# Schem_fcvv01.net
KiCad netlist of a schematic drawn in Altium Designer
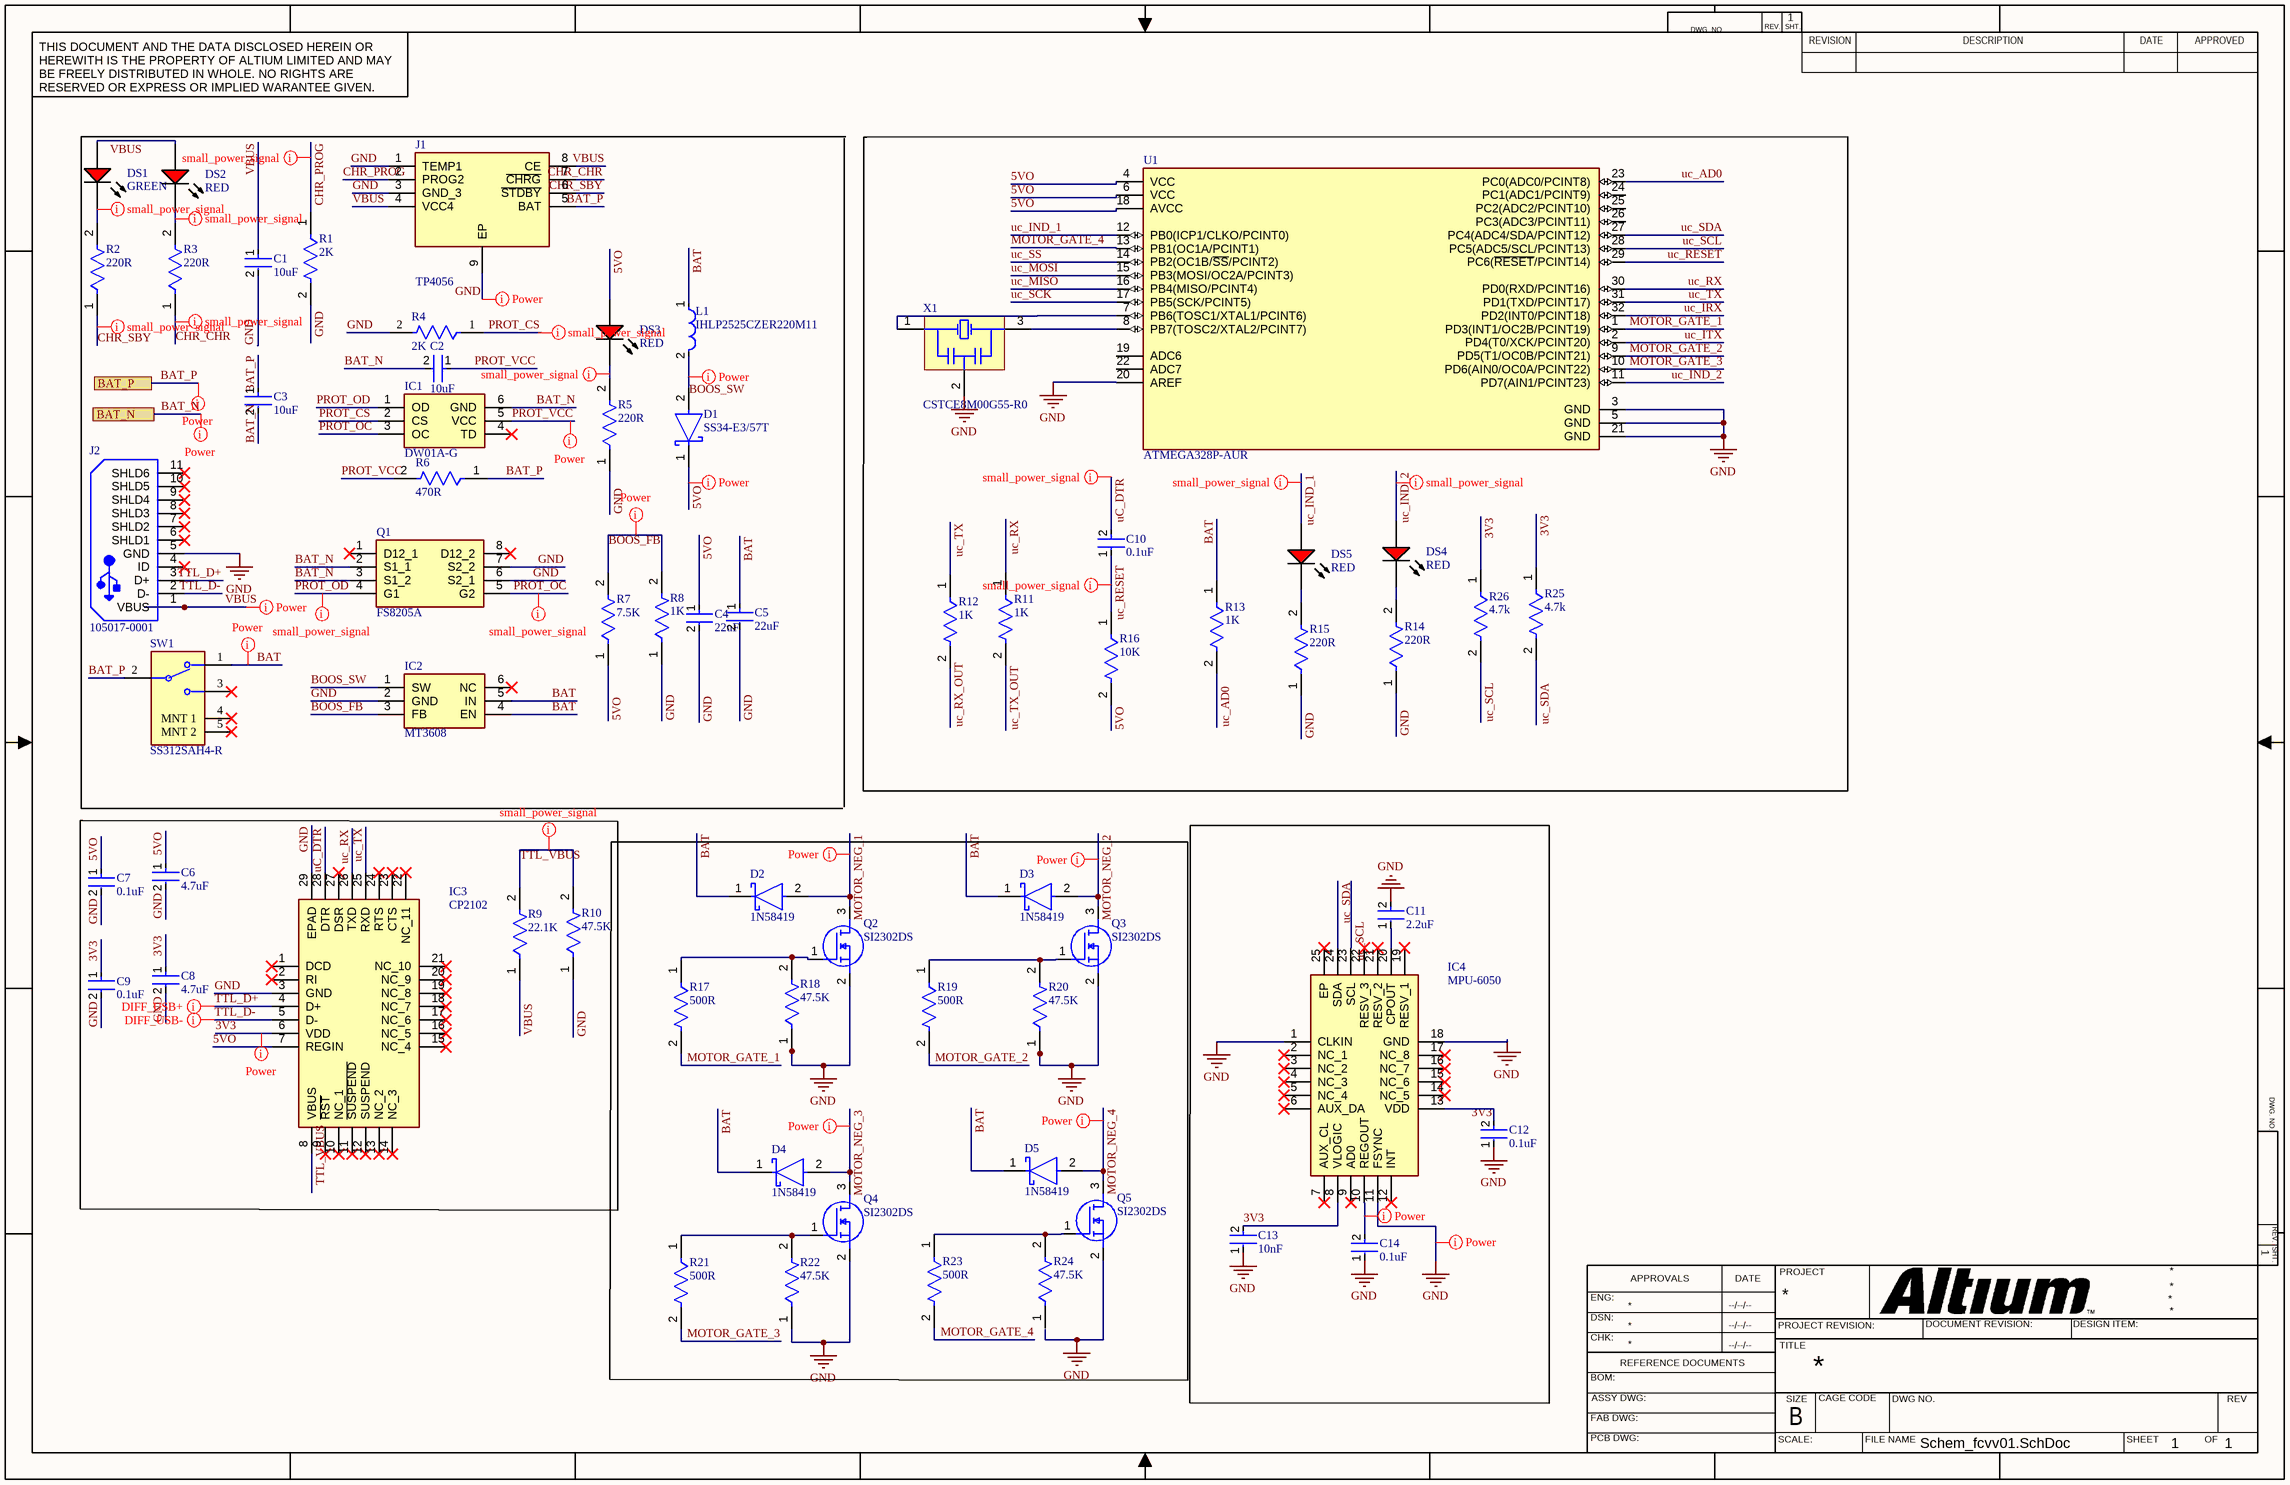
[diagram p0: Schem_fcvv01.SchDoc]

(export (version "E")
  (design (tool "Eeschema 10.0.6"))
  (components
    (comp (ref "C1")
      (value "10uF")
      (footprint "FP-GRM188-0_1-e0_2_0_55-IPC_A")
      (description "10uF 0603")
      (fields (field (name "VOLTAGE") "6.3V") (field (name "TOLERANCE") "20%"))
      (libsource (lib "Altium Content Vault") (part "02cd4be3c70576c341d710602a673aa"))
    )
    (comp (ref "C2")
      (value "10uF")
      (footprint "FP-GRM188-0_1-e0_2_0_55-IPC_A")
      (description "10uF 0603")
      (fields (field (name "VOLTAGE") "6.3V") (field (name "TOLERANCE") "20%"))
      (libsource (lib "Altium Content Vault") (part "02cd4be3c70576c341d710602a673aa"))
    )
    (comp (ref "C3")
      (value "10uF")
      (footprint "FP-GRM188-0_1-e0_2_0_55-IPC_A")
      (description "0603")
      (fields (field (name "VOLTAGE") "6.3V") (field (name "TOLERANCE") "20%"))
      (libsource (lib "Altium Content Vault") (part "02cd4be3c70576c341d710602a673aa"))
    )
    (comp (ref "C4")
      (value "22uF")
      (footprint "FP-GRM188-0_1-e0_2_0_55-IPC_A")
      (description "10uF 0603")
      (fields (field (name "VOLTAGE") "6.3V") (field (name "TOLERANCE") "20%"))
      (libsource (lib "Altium Content Vault") (part "02cd4be3c70576c341d710602a673aa"))
    )
    (comp (ref "C5")
      (value "22uF")
      (footprint "FP-GRM188-0_1-e0_2_0_55-IPC_A")
      (description "10uF 0603")
      (fields (field (name "VOLTAGE") "6.3V") (field (name "TOLERANCE") "20%"))
      (libsource (lib "Altium Content Vault") (part "02cd4be3c70576c341d710602a673aa"))
    )
    (comp (ref "C6")
      (value "4.7uF")
      (footprint "FP-GRM188-0_1-e0_2_0_55-IPC_A")
      (description "0603")
      (fields (field (name "VOLTAGE") "6.3V") (field (name "TOLERANCE") "20%"))
      (libsource (lib "Altium Content Vault") (part "02cd4be3c70576c341d710602a673aa"))
    )
    (comp (ref "C7")
      (value "0.1uF")
      (footprint "FP-GRM188-0_1-e0_2_0_55-IPC_A")
      (description "0603")
      (fields (field (name "VOLTAGE") "6.3V") (field (name "TOLERANCE") "20%"))
      (libsource (lib "Altium Content Vault") (part "02cd4be3c70576c341d710602a673aa"))
    )
    (comp (ref "C8")
      (value "4.7uF")
      (footprint "FP-GRM188-0_1-e0_2_0_55-IPC_A")
      (description "0603")
      (fields (field (name "VOLTAGE") "6.3V") (field (name "TOLERANCE") "20%"))
      (libsource (lib "Altium Content Vault") (part "02cd4be3c70576c341d710602a673aa"))
    )
    (comp (ref "C9")
      (value "0.1uF")
      (footprint "FP-GRM188-0_1-e0_2_0_55-IPC_A")
      (description "0603")
      (fields (field (name "VOLTAGE") "6.3V") (field (name "TOLERANCE") "20%"))
      (libsource (lib "Altium Content Vault") (part "02cd4be3c70576c341d710602a673aa"))
    )
    (comp (ref "C10")
      (value "0.1uF")
      (footprint "FP-GRM15-MFG")
      (description "CAP CER 0.1UF 16V X7R 0402")
      (fields (field (name "MANUFACTURER PART NUMBER") "GRM155R71C104KA88D") (field (name "TOLERANCE") "10%"))
      (libsource (lib "Altium Content Vault") (part "236180d848d6139a670b325ea6854c9"))
    )
    (comp (ref "C11")
      (value "2.2uF")
      (footprint "FP-GRM15-MFG")
      (description "CAP CER 0.1UF 16V X7R 0402")
      (fields (field (name "MANUFACTURER PART NUMBER") "GRM155R71C104KA88D") (field (name "TOLERANCE") "10%"))
      (libsource (lib "Altium Content Vault") (part "236180d848d6139a670b325ea6854c9"))
    )
    (comp (ref "C12")
      (value "0.1uF")
      (footprint "FP-GRM15-MFG")
      (description "CAP CER 0.1UF 16V X7R 0402")
      (fields (field (name "MANUFACTURER PART NUMBER") "GRM155R71C104KA88D") (field (name "TOLERANCE") "10%"))
      (libsource (lib "Altium Content Vault") (part "236180d848d6139a670b325ea6854c9"))
    )
    (comp (ref "C13")
      (value "10nF")
      (footprint "FP-GRM15-MFG")
      (description "CAP CER 0.1UF 16V X7R 0402")
      (fields (field (name "MANUFACTURER PART NUMBER") "GRM155R71C104KA88D") (field (name "TOLERANCE") "10%"))
      (libsource (lib "Altium Content Vault") (part "236180d848d6139a670b325ea6854c9"))
    )
    (comp (ref "C14")
      (value "0.1uF")
      (footprint "FP-GRM15-MFG")
      (description "CAP CER 0.1UF 16V X7R 0402")
      (fields (field (name "MANUFACTURER PART NUMBER") "GRM155R71C104KA88D") (field (name "TOLERANCE") "10%"))
      (libsource (lib "Altium Content Vault") (part "236180d848d6139a670b325ea6854c9"))
    )
    (comp (ref "D1")
      (value "SS34-E3/57T")
      (footprint "FP-95402-MFG")
      (description "DIODE SCHOTTKY 40V 3A DO214AB")
      (fields
        (field (name "MANUFACTURER") "Vishay")
        (field (name "OCTOPART") "https://octopart.com/ss34-e3%2F57t-vishay-39552907")
      )
      (libsource (lib "Altium Content Vault") (part "1d6ec82d83fb6aee721767c19dac4b9"))
    )
    (comp (ref "D2")
      (value "1N58419")
      (footprint "FP-425-04-IPC_C")
      (description "DIODE SCHOTTKY 20V 500MA SOD123")
      (libsource (lib "Altium Content Vault") (part "1d6ec82d83fb6aee721767c19dac4b9"))
    )
    (comp (ref "D3")
      (value "1N58419")
      (footprint "FP-425-04-IPC_C")
      (description "DIODE SCHOTTKY 20V 500MA SOD123")
      (libsource (lib "Altium Content Vault") (part "1d6ec82d83fb6aee721767c19dac4b9"))
    )
    (comp (ref "D4")
      (value "1N58419")
      (footprint "FP-425-04-IPC_C")
      (description "DIODE SCHOTTKY 20V 500MA SOD123")
      (libsource (lib "Altium Content Vault") (part "1d6ec82d83fb6aee721767c19dac4b9"))
    )
    (comp (ref "D5")
      (value "1N58419")
      (footprint "FP-425-04-IPC_C")
      (description "DIODE SCHOTTKY 20V 500MA SOD123")
      (libsource (lib "Altium Content Vault") (part "1d6ec82d83fb6aee721767c19dac4b9"))
    )
    (comp (ref "DS1")
      (value "GREEN")
      (footprint "VISH-TLMX1100_V")
      (description "Red 0603 Light Emitting Diodes (LED) ROHS/NCD0603R1")
      (fields (field (name "TOLERANCE") "5%"))
      (libsource (lib "Altium Content Vault") (part "LED-RED-AK-2"))
    )
    (comp (ref "DS2")
      (value "RED")
      (footprint "VISH-TLMX1100_V")
      (description "Red 0603 Light Emitting Diodes (LED) ROHS/NCD0603R1")
      (fields (field (name "TOLERANCE") "5%"))
      (libsource (lib "Altium Content Vault") (part "LED-RED-AK-2"))
    )
    (comp (ref "DS3")
      (value "RED")
      (footprint "VISH-TLMX1100_V")
      (description "Red 0603 Light Emitting Diodes (LED) ROHS/NCD0603R1")
      (fields (field (name "TOLERANCE") "5%"))
      (libsource (lib "Altium Content Vault") (part "LED-RED-AK-2"))
    )
    (comp (ref "DS4")
      (value "RED")
      (footprint "VISH-TLMX1100_V")
      (description "Red 0603 Light Emitting Diodes (LED) ROHS/NCD0603R1")
      (fields (field (name "TOLERANCE") "5%"))
      (libsource (lib "Altium Content Vault") (part "LED-RED-AK-2"))
    )
    (comp (ref "DS5")
      (value "RED")
      (footprint "VISH-TLMX1100_V")
      (description "Red 0603 Light Emitting Diodes (LED) ROHS/NCD0603R1")
      (fields (field (name "TOLERANCE") "5%"))
      (libsource (lib "Altium Content Vault") (part "LED-RED-AK-2"))
    )
    (comp (ref "IC1")
      (value "DW01A-G")
      (footprint "PcbLib:SOT95P280X135-6N")
      (description "Integrated Circuit")
      (libsource (lib "Schlib") (part "DW01A-G"))
    )
    (comp (ref "IC2")
      (value "MT3608")
      (footprint "PcbLib:SOT95P280X145-6N")
      (description "Integrated Circuit")
      (libsource (lib "Schlib") (part "MT3608"))
    )
    (comp (ref "IC3")
      (value "CP2102")
      (footprint "SamacSys:QFN50P500X500X100-29N-D")
      (description "Integrated Circuit")
      (fields (field (name "MOUSER PART NUMBER") "634-CP2102"))
      (libsource (lib "*") (part "CP2102"))
    )
    (comp (ref "IC4")
      (value "MPU-6050")
      (footprint "PcbLib:MPU6050")
      (description "Integrated Circuit")
      (fields (field (name "MOUSER PART NUMBER") "410-MPU-6050"))
      (libsource (lib "Schlib") (part "MPU-6050"))
    )
    (comp (ref "J1")
      (value "TP4056")
      (footprint "PcbLib:SOIC127P600X175-9N")
      (description "Connector")
      (libsource (lib "Schlib") (part "TP4056"))
    )
    (comp (ref "J2")
      (value "105017-0001")
      (footprint "USB-MICRO-B_V")
      (fields (field (name "MANUFACTURER") "Molex"))
      (libsource (lib "Altium Content Vault") (part "USB-5-6SHLD"))
    )
    (comp (ref "L1")
      (value "IHLP2525CZER220M11")
      (footprint "FP-IHLP-2525CZ-FP_2_413x3-MFG")
      (description "Commercial Inductors, Low DCR Series 22uH 2.9A 135mΩ 20%")
      (fields (field (name "TOLERANCE") "20%"))
      (libsource (lib "Altium Content Vault") (part "725321dda6339637d4d059423bc1c3c"))
    )
    (comp (ref "Q1")
      (value "FS8205A")
      (footprint "PcbLib:SOP65P640X120-8N")
      (description "Transistor")
      (libsource (lib "Schlib") (part "FS8205A"))
    )
    (comp (ref "Q2")
      (value "SI2302DS")
      (footprint "PcbLib:SOT95P230X110-3N")
      (description "MOSFET (N-Channel)")
      (libsource (lib "Schlib") (part "SI2302DS"))
    )
    (comp (ref "Q3")
      (value "SI2302DS")
      (footprint "PcbLib:SOT95P230X110-3N")
      (description "MOSFET (N-Channel)")
      (libsource (lib "Schlib") (part "SI2302DS"))
    )
    (comp (ref "Q4")
      (value "SI2302DS")
      (footprint "PcbLib:SOT95P230X110-3N")
      (description "MOSFET (N-Channel)")
      (libsource (lib "Schlib") (part "SI2302DS"))
    )
    (comp (ref "Q5")
      (value "SI2302DS")
      (footprint "PcbLib:SOT95P230X110-3N")
      (description "MOSFET (N-Channel)")
      (libsource (lib "Schlib") (part "SI2302DS"))
    )
    (comp (ref "R1")
      (value "2K")
      (footprint "FP-CRCW0402-e3-IPC_C")
      (fields (field (name "TOLERANCE") "5%"))
      (libsource (lib "Altium Content Vault") (part "1029c3af85768c4190bb7ad29bc67b5"))
    )
    (comp (ref "R2")
      (value "220R")
      (footprint "FP-CRCW0402-e3-IPC_C")
      (fields (field (name "TOLERANCE") "5%"))
      (libsource (lib "Altium Content Vault") (part "1029c3af85768c4190bb7ad29bc67b5"))
    )
    (comp (ref "R3")
      (value "220R")
      (footprint "FP-CRCW0402-e3-IPC_C")
      (fields (field (name "TOLERANCE") "5%"))
      (libsource (lib "Altium Content Vault") (part "1029c3af85768c4190bb7ad29bc67b5"))
    )
    (comp (ref "R4")
      (value "2K")
      (footprint "FP-ERA3A-IPC_C")
      (fields (field (name "TOLERANCE") "0.1%"))
      (libsource (lib "Altium Content Vault") (part "4e5f8b3dd332802e91518312df5df73"))
    )
    (comp (ref "R5")
      (value "220R")
      (footprint "FP-CRCW0402-e3-IPC_C")
      (fields (field (name "TOLERANCE") "5%"))
      (libsource (lib "Altium Content Vault") (part "1029c3af85768c4190bb7ad29bc67b5"))
    )
    (comp (ref "R6")
      (value "470R")
      (footprint "FP-CRCW0402-e3-IPC_C")
      (fields (field (name "TOLERANCE") "5%"))
      (libsource (lib "Altium Content Vault") (part "1029c3af85768c4190bb7ad29bc67b5"))
    )
    (comp (ref "R7")
      (value "7.5K")
      (footprint "FP-CRCW0402-e3-IPC_C")
      (fields (field (name "TOLERANCE") "5%"))
      (libsource (lib "Altium Content Vault") (part "1029c3af85768c4190bb7ad29bc67b5"))
    )
    (comp (ref "R8")
      (value "1K")
      (footprint "FP-CRCW0402-e3-IPC_C")
      (fields (field (name "TOLERANCE") "5%"))
      (libsource (lib "Altium Content Vault") (part "1029c3af85768c4190bb7ad29bc67b5"))
    )
    (comp (ref "R9")
      (value "22.1K")
      (footprint "FP-CRCW0402-e3-IPC_C")
      (fields (field (name "TOLERANCE") "5%"))
      (libsource (lib "Altium Content Vault") (part "1029c3af85768c4190bb7ad29bc67b5"))
    )
    (comp (ref "R10")
      (value "47.5K")
      (footprint "FP-CRCW0402-e3-IPC_C")
      (fields (field (name "TOLERANCE") "5%"))
      (libsource (lib "Altium Content Vault") (part "1029c3af85768c4190bb7ad29bc67b5"))
    )
    (comp (ref "R11")
      (value "1K")
      (footprint "FP-CRCW0402-e3-IPC_C")
      (fields (field (name "TOLERANCE") "5%"))
      (libsource (lib "Altium Content Vault") (part "1029c3af85768c4190bb7ad29bc67b5"))
    )
    (comp (ref "R12")
      (value "1K")
      (footprint "FP-CRCW0402-e3-IPC_C")
      (fields (field (name "TOLERANCE") "5%"))
      (libsource (lib "Altium Content Vault") (part "1029c3af85768c4190bb7ad29bc67b5"))
    )
    (comp (ref "R13")
      (value "1K")
      (footprint "FP-CRCW0402-e3-IPC_C")
      (fields (field (name "TOLERANCE") "5%"))
      (libsource (lib "Altium Content Vault") (part "1029c3af85768c4190bb7ad29bc67b5"))
    )
    (comp (ref "R14")
      (value "220R")
      (footprint "FP-CRCW0402-e3-IPC_C")
      (fields (field (name "TOLERANCE") "5%"))
      (libsource (lib "Altium Content Vault") (part "1029c3af85768c4190bb7ad29bc67b5"))
    )
    (comp (ref "R15")
      (value "220R")
      (footprint "FP-CRCW0402-e3-IPC_C")
      (fields (field (name "TOLERANCE") "5%"))
      (libsource (lib "Altium Content Vault") (part "1029c3af85768c4190bb7ad29bc67b5"))
    )
    (comp (ref "R16")
      (value "10K")
      (footprint "FP-CRCW0402-e3-IPC_C")
      (fields (field (name "TOLERANCE") "5%"))
      (libsource (lib "Altium Content Vault") (part "1029c3af85768c4190bb7ad29bc67b5"))
    )
    (comp (ref "R17")
      (value "500R")
      (footprint "FP-CRCW0402-e3-IPC_C")
      (fields (field (name "TOLERANCE") "5%"))
      (libsource (lib "Altium Content Vault") (part "1029c3af85768c4190bb7ad29bc67b5"))
    )
    (comp (ref "R18")
      (value "47.5K")
      (footprint "FP-CRCW0402-e3-IPC_C")
      (fields (field (name "TOLERANCE") "5%"))
      (libsource (lib "Altium Content Vault") (part "1029c3af85768c4190bb7ad29bc67b5"))
    )
    (comp (ref "R19")
      (value "500R")
      (footprint "FP-CRCW0402-e3-IPC_C")
      (fields (field (name "TOLERANCE") "5%"))
      (libsource (lib "Altium Content Vault") (part "1029c3af85768c4190bb7ad29bc67b5"))
    )
    (comp (ref "R20")
      (value "47.5K")
      (footprint "FP-CRCW0402-e3-IPC_C")
      (fields (field (name "TOLERANCE") "5%"))
      (libsource (lib "Altium Content Vault") (part "1029c3af85768c4190bb7ad29bc67b5"))
    )
    (comp (ref "R21")
      (value "500R")
      (footprint "FP-CRCW0402-e3-IPC_C")
      (fields (field (name "TOLERANCE") "5%"))
      (libsource (lib "Altium Content Vault") (part "1029c3af85768c4190bb7ad29bc67b5"))
    )
    (comp (ref "R22")
      (value "47.5K")
      (footprint "FP-CRCW0402-e3-IPC_C")
      (fields (field (name "TOLERANCE") "5%"))
      (libsource (lib "Altium Content Vault") (part "1029c3af85768c4190bb7ad29bc67b5"))
    )
    (comp (ref "R23")
      (value "500R")
      (footprint "FP-CRCW0402-e3-IPC_C")
      (fields (field (name "TOLERANCE") "5%"))
      (libsource (lib "Altium Content Vault") (part "1029c3af85768c4190bb7ad29bc67b5"))
    )
    (comp (ref "R24")
      (value "47.5K")
      (footprint "FP-CRCW0402-e3-IPC_C")
      (fields (field (name "TOLERANCE") "5%"))
      (libsource (lib "Altium Content Vault") (part "1029c3af85768c4190bb7ad29bc67b5"))
    )
    (comp (ref "R25")
      (value "4.7k")
      (footprint "FP-CRCW0402-e3-IPC_C")
      (fields (field (name "TOLERANCE") "5%"))
      (libsource (lib "Altium Content Vault") (part "1029c3af85768c4190bb7ad29bc67b5"))
    )
    (comp (ref "R26")
      (value "4.7k")
      (footprint "FP-CRCW0402-e3-IPC_C")
      (fields (field (name "TOLERANCE") "5%"))
      (libsource (lib "Altium Content Vault") (part "1029c3af85768c4190bb7ad29bc67b5"))
    )
    (comp (ref "SW1")
      (value "SS312SAH4-R")
      (footprint "FP-SS312SAH4-R-MFG")
      (description "SWITCH SLIDE SPDT 0.4VA 28V")
      (libsource (lib "Altium Content Vault") (part "4c976abc4051e389b5557946779e9a3"))
    )
    (comp (ref "U1")
      (value "ATMEGA328P-AUR")
      (footprint "FP-32A-IPC_C")
      (description "IC MCU 8BIT 32KB FLASH 32TQFP")
      (libsource (lib "Altium Content Vault") (part "a21e5c44209584805972c9959ca5560"))
    )
    (comp (ref "X1")
      (value "CSTCE8M00G55-R0")
      (footprint "MURA-CSTCE_G_A-3_V")
      (description "Ceramic Resonator, 8 MHz, +/- 0.5%, -20 to 80 degC, 3-Pin SMD, RoHS, Tape and Reel")
      (fields (field (name "TOLERANCE") "0.5%") (field (name "MANUFACTURER") "Murata"))
      (libsource (lib "Altium Content Vault") (part "MURA-CSTCE_G_A-3"))
    )
  )
  (nets
    (net (code "1") (name "/3V3") (class "Default")
      (node (ref "C12") (pin "2") (pinfunction "2_2") (pintype "passive"))
      (node (ref "C13") (pin "2") (pinfunction "2_2") (pintype "passive"))
      (node (ref "C8") (pin "1") (pinfunction "1_1") (pintype "passive"))
      (node (ref "C9") (pin "1") (pinfunction "1_1") (pintype "passive"))
      (node (ref "IC3") (pin "6") (pinfunction "VDD_6") (pintype "passive"))
      (node (ref "IC4") (pin "13") (pinfunction "VDD_13") (pintype "passive"))
      (node (ref "IC4") (pin "8") (pinfunction "VLOGIC_8") (pintype "passive"))
      (node (ref "R25") (pin "1") (pinfunction "1_1") (pintype "passive"))
      (node (ref "R26") (pin "1") (pinfunction "1_1") (pintype "passive"))
    )
    (net (code "2") (name "/5VO") (class "Default")
      (node (ref "C4") (pin "1") (pinfunction "1_1") (pintype "passive"))
      (node (ref "C6") (pin "1") (pinfunction "1_1") (pintype "passive"))
      (node (ref "C7") (pin "1") (pinfunction "1_1") (pintype "passive"))
      (node (ref "D1") (pin "1") (pinfunction "C_1") (pintype "passive"))
      (node (ref "DS3") (pin "1") (pinfunction "A_1") (pintype "passive"))
      (node (ref "IC3") (pin "7") (pinfunction "REGIN_7") (pintype "passive"))
      (node (ref "R16") (pin "2") (pinfunction "2_2") (pintype "passive"))
      (node (ref "R7") (pin "1") (pinfunction "1_1") (pintype "passive"))
      (node (ref "U1") (pin "18") (pinfunction "AVCC_18") (pintype "power_in"))
      (node (ref "U1") (pin "4") (pinfunction "VCC_4") (pintype "power_in"))
      (node (ref "U1") (pin "6") (pinfunction "VCC_6") (pintype "power_in"))
    )
    (net (code "3") (name "/BAT") (class "Default")
      (node (ref "C5") (pin "1") (pinfunction "1_1") (pintype "passive"))
      (node (ref "D2") (pin "1") (pinfunction "C_1") (pintype "passive"))
      (node (ref "D3") (pin "1") (pinfunction "C_1") (pintype "passive"))
      (node (ref "D4") (pin "1") (pinfunction "C_1") (pintype "passive"))
      (node (ref "D5") (pin "1") (pinfunction "C_1") (pintype "passive"))
      (node (ref "IC2") (pin "4") (pinfunction "EN_4") (pintype "passive"))
      (node (ref "IC2") (pin "5") (pinfunction "IN_5") (pintype "passive"))
      (node (ref "L1") (pin "1") (pinfunction "1_1") (pintype "passive"))
      (node (ref "R13") (pin "1") (pinfunction "1_1") (pintype "passive"))
      (node (ref "SW1") (pin "1") (pinfunction "1_1") (pintype "passive"))
    )
    (net (code "4") (name "/BAT_N") (class "Default")
      (node (ref "C2") (pin "2") (pinfunction "2_2") (pintype "passive"))
      (node (ref "C3") (pin "2") (pinfunction "2_2") (pintype "passive"))
      (node (ref "IC1") (pin "6") (pinfunction "GND_6") (pintype "passive"))
      (node (ref "Q1") (pin "2") (pinfunction "S1_1_2") (pintype "passive"))
      (node (ref "Q1") (pin "3") (pinfunction "S1_2_3") (pintype "passive"))
    )
    (net (code "5") (name "/BAT_P") (class "Default")
      (node (ref "C3") (pin "1") (pinfunction "1_1") (pintype "passive"))
      (node (ref "J1") (pin "5") (pinfunction "BAT_5") (pintype "passive"))
      (node (ref "R6") (pin "1") (pinfunction "1_1") (pintype "passive"))
      (node (ref "SW1") (pin "2") (pinfunction "COM_2") (pintype "passive"))
    )
    (net (code "6") (name "/BOOS_FB") (class "Default")
      (node (ref "IC2") (pin "3") (pinfunction "FB_3") (pintype "passive"))
      (node (ref "R7") (pin "2") (pinfunction "2_2") (pintype "passive"))
      (node (ref "R8") (pin "2") (pinfunction "2_2") (pintype "passive"))
    )
    (net (code "7") (name "/BOOS_SW") (class "Default")
      (node (ref "D1") (pin "2") (pinfunction "A_2") (pintype "passive"))
      (node (ref "IC2") (pin "1") (pinfunction "SW_1") (pintype "passive"))
      (node (ref "L1") (pin "2") (pinfunction "2_2") (pintype "passive"))
    )
    (net (code "8") (name "/CHR_CHR") (class "Default")
      (node (ref "J1") (pin "7") (pinfunction "~{CHRG}_7") (pintype "passive"))
      (node (ref "R3") (pin "1") (pinfunction "1_1") (pintype "passive"))
    )
    (net (code "9") (name "/CHR_PROG") (class "Default")
      (node (ref "J1") (pin "2") (pinfunction "PROG2_2") (pintype "passive"))
      (node (ref "R1") (pin "1") (pinfunction "1_1") (pintype "passive"))
    )
    (net (code "10") (name "/CHR_SBY") (class "Default")
      (node (ref "J1") (pin "6") (pinfunction "~{STDBY}_6") (pintype "passive"))
      (node (ref "R2") (pin "1") (pinfunction "1_1") (pintype "passive"))
    )
    (net (code "11") (name "/MOTOR_GATE_1") (class "Default")
      (node (ref "R17") (pin "2") (pinfunction "2_2") (pintype "passive"))
      (node (ref "U1") (pin "1") (pinfunction "PD3(INT1/OC2B/PCINT19)_1") (pintype "bidirectional"))
    )
    (net (code "12") (name "/MOTOR_GATE_2") (class "Default")
      (node (ref "R19") (pin "2") (pinfunction "2_2") (pintype "passive"))
      (node (ref "U1") (pin "9") (pinfunction "PD5(T1/OC0B/PCINT21)_9") (pintype "bidirectional"))
    )
    (net (code "13") (name "/MOTOR_GATE_3") (class "Default")
      (node (ref "R21") (pin "2") (pinfunction "2_2") (pintype "passive"))
      (node (ref "U1") (pin "10") (pinfunction "PD6(AIN0/OC0A/PCINT22)_10") (pintype "bidirectional"))
    )
    (net (code "14") (name "/MOTOR_GATE_4") (class "Default")
      (node (ref "R23") (pin "2") (pinfunction "2_2") (pintype "passive"))
      (node (ref "U1") (pin "13") (pinfunction "PB1(OC1A/PCINT1)_13") (pintype "bidirectional"))
    )
    (net (code "15") (name "/MOTOR_NEG_1") (class "Default")
      (node (ref "D2") (pin "2") (pinfunction "A_2") (pintype "passive"))
      (node (ref "Q2") (pin "3") (pinfunction "D_3") (pintype "passive"))
    )
    (net (code "16") (name "/MOTOR_NEG_2") (class "Default")
      (node (ref "D3") (pin "2") (pinfunction "A_2") (pintype "passive"))
      (node (ref "Q3") (pin "3") (pinfunction "D_3") (pintype "passive"))
    )
    (net (code "17") (name "/MOTOR_NEG_3") (class "Default")
      (node (ref "D4") (pin "2") (pinfunction "A_2") (pintype "passive"))
      (node (ref "Q4") (pin "3") (pinfunction "D_3") (pintype "passive"))
    )
    (net (code "18") (name "/MOTOR_NEG_4") (class "Default")
      (node (ref "D5") (pin "2") (pinfunction "A_2") (pintype "passive"))
      (node (ref "Q5") (pin "3") (pinfunction "D_3") (pintype "passive"))
    )
    (net (code "19") (name "/PROT_CS") (class "Default")
      (node (ref "IC1") (pin "2") (pinfunction "CS_2") (pintype "passive"))
      (node (ref "R4") (pin "1") (pinfunction "1_1") (pintype "passive"))
    )
    (net (code "20") (name "/PROT_OC") (class "Default")
      (node (ref "IC1") (pin "3") (pinfunction "OC_3") (pintype "passive"))
      (node (ref "Q1") (pin "5") (pinfunction "G2_5") (pintype "passive"))
    )
    (net (code "21") (name "/PROT_OD") (class "Default")
      (node (ref "IC1") (pin "1") (pinfunction "OD_1") (pintype "passive"))
      (node (ref "Q1") (pin "4") (pinfunction "G1_4") (pintype "passive"))
    )
    (net (code "22") (name "/PROT_VCC") (class "Default")
      (node (ref "C2") (pin "1") (pinfunction "1_1") (pintype "passive"))
      (node (ref "IC1") (pin "5") (pinfunction "VCC_5") (pintype "passive"))
      (node (ref "R6") (pin "2") (pinfunction "2_2") (pintype "passive"))
    )
    (net (code "23") (name "/TTL_D+") (class "Default")
      (node (ref "IC3") (pin "4") (pinfunction "D+_4") (pintype "passive"))
      (node (ref "J2") (pin "3") (pinfunction "D+_3") (pintype "passive"))
    )
    (net (code "24") (name "/TTL_D-") (class "Default")
      (node (ref "IC3") (pin "5") (pinfunction "D-_5") (pintype "passive"))
      (node (ref "J2") (pin "2") (pinfunction "D-_2") (pintype "passive"))
    )
    (net (code "25") (name "/TTL_VBUS") (class "Default")
      (node (ref "IC3") (pin "8") (pinfunction "VBUS_8") (pintype "passive"))
      (node (ref "R10") (pin "2") (pinfunction "2_2") (pintype "passive"))
      (node (ref "R9") (pin "2") (pinfunction "2_2") (pintype "passive"))
    )
    (net (code "26") (name "/VBUS") (class "Default")
      (node (ref "C1") (pin "1") (pinfunction "1_1") (pintype "passive"))
      (node (ref "DS1") (pin "1") (pinfunction "A_1") (pintype "passive"))
      (node (ref "DS2") (pin "1") (pinfunction "A_1") (pintype "passive"))
      (node (ref "J1") (pin "4") (pinfunction "VCC4_4") (pintype "passive"))
      (node (ref "J1") (pin "8") (pinfunction "CE_8") (pintype "passive"))
      (node (ref "J2") (pin "1") (pinfunction "VBUS_1") (pintype "passive"))
      (node (ref "R9") (pin "1") (pinfunction "1_1") (pintype "passive"))
    )
    (net (code "27") (name "/uC_DTR") (class "Default")
      (node (ref "C10") (pin "2") (pinfunction "2_2") (pintype "passive"))
      (node (ref "IC3") (pin "28") (pinfunction "DTR_28") (pintype "passive"))
    )
    (net (code "28") (name "/uc_AD0") (class "Default")
      (node (ref "R13") (pin "2") (pinfunction "2_2") (pintype "passive"))
      (node (ref "U1") (pin "23") (pinfunction "PC0(ADC0/PCINT8)_23") (pintype "bidirectional"))
    )
    (net (code "29") (name "/uc_IND_1") (class "Default")
      (node (ref "DS5") (pin "1") (pinfunction "A_1") (pintype "passive"))
      (node (ref "U1") (pin "12") (pinfunction "PB0(ICP1/CLKO/PCINT0)_12") (pintype "bidirectional"))
    )
    (net (code "30") (name "/uc_IND_2") (class "Default")
      (node (ref "DS4") (pin "1") (pinfunction "A_1") (pintype "passive"))
      (node (ref "U1") (pin "11") (pinfunction "PD7(AIN1/PCINT23)_11") (pintype "bidirectional"))
    )
    (net (code "31") (name "/uc_IRX") (class "Default")
      (node (ref "U1") (pin "32") (pinfunction "PD2(INT0/PCINT18)_32") (pintype "bidirectional"))
    )
    (net (code "32") (name "/uc_ITX") (class "Default")
      (node (ref "U1") (pin "2") (pinfunction "PD4(T0/XCK/PCINT20)_2") (pintype "bidirectional"))
    )
    (net (code "33") (name "/uc_MISO") (class "Default")
      (node (ref "U1") (pin "16") (pinfunction "PB4(MISO/PCINT4)_16") (pintype "bidirectional"))
    )
    (net (code "34") (name "/uc_MOSI") (class "Default")
      (node (ref "U1") (pin "15") (pinfunction "PB3(MOSI/OC2A/PCINT3)_15") (pintype "bidirectional"))
    )
    (net (code "35") (name "/uc_RESET") (class "Default")
      (node (ref "C10") (pin "1") (pinfunction "1_1") (pintype "passive"))
      (node (ref "R16") (pin "1") (pinfunction "1_1") (pintype "passive"))
      (node (ref "U1") (pin "29") (pinfunction "PC6(~{RESET}/PCINT14)_29") (pintype "bidirectional"))
    )
    (net (code "36") (name "/uc_RX") (class "Default")
      (node (ref "IC3") (pin "26") (pinfunction "TXD_26") (pintype "passive"))
      (node (ref "R11") (pin "1") (pinfunction "1_1") (pintype "passive"))
      (node (ref "U1") (pin "30") (pinfunction "PD0(RXD/PCINT16)_30") (pintype "bidirectional"))
    )
    (net (code "37") (name "/uc_RX_OUT") (class "Default")
      (node (ref "R12") (pin "2") (pinfunction "2_2") (pintype "passive"))
    )
    (net (code "38") (name "/uc_SCK") (class "Default")
      (node (ref "U1") (pin "17") (pinfunction "PB5(SCK/PCINT5)_17") (pintype "bidirectional"))
    )
    (net (code "39") (name "/uc_SCL") (class "Default")
      (node (ref "IC4") (pin "23") (pinfunction "SCL_23") (pintype "passive"))
      (node (ref "R26") (pin "2") (pinfunction "2_2") (pintype "passive"))
      (node (ref "U1") (pin "28") (pinfunction "PC5(ADC5/SCL/PCINT13)_28") (pintype "bidirectional"))
    )
    (net (code "40") (name "/uc_SDA") (class "Default")
      (node (ref "IC4") (pin "24") (pinfunction "SDA_24") (pintype "passive"))
      (node (ref "R25") (pin "2") (pinfunction "2_2") (pintype "passive"))
      (node (ref "U1") (pin "27") (pinfunction "PC4(ADC4/SDA/PCINT12)_27") (pintype "bidirectional"))
    )
    (net (code "41") (name "/uc_SS") (class "Default")
      (node (ref "U1") (pin "14") (pinfunction "PB2(OC1B/~{SS}/PCINT2)_14") (pintype "bidirectional"))
    )
    (net (code "42") (name "/uc_TX") (class "Default")
      (node (ref "IC3") (pin "25") (pinfunction "RXD_25") (pintype "passive"))
      (node (ref "R12") (pin "1") (pinfunction "1_1") (pintype "passive"))
      (node (ref "U1") (pin "31") (pinfunction "PD1(TXD/PCINT17)_31") (pintype "bidirectional"))
    )
    (net (code "43") (name "/uc_TX_OUT") (class "Default")
      (node (ref "R11") (pin "2") (pinfunction "2_2") (pintype "passive"))
    )
    (net (code "44") (name "GND") (class "Default")
      (node (ref "C1") (pin "2") (pinfunction "2_2") (pintype "passive"))
      (node (ref "C11") (pin "2") (pinfunction "2_2") (pintype "passive"))
      (node (ref "C12") (pin "1") (pinfunction "1_1") (pintype "passive"))
      (node (ref "C13") (pin "1") (pinfunction "1_1") (pintype "passive"))
      (node (ref "C14") (pin "1") (pinfunction "1_1") (pintype "passive"))
      (node (ref "C4") (pin "2") (pinfunction "2_2") (pintype "passive"))
      (node (ref "C5") (pin "2") (pinfunction "2_2") (pintype "passive"))
      (node (ref "C6") (pin "2") (pinfunction "2_2") (pintype "passive"))
      (node (ref "C7") (pin "2") (pinfunction "2_2") (pintype "passive"))
      (node (ref "C8") (pin "2") (pinfunction "2_2") (pintype "passive"))
      (node (ref "C9") (pin "2") (pinfunction "2_2") (pintype "passive"))
      (node (ref "IC2") (pin "2") (pinfunction "GND_2") (pintype "passive"))
      (node (ref "IC3") (pin "29") (pinfunction "EPAD_29") (pintype "passive"))
      (node (ref "IC3") (pin "3") (pinfunction "GND_3") (pintype "passive"))
      (node (ref "IC4") (pin "1") (pinfunction "CLKIN_1") (pintype "passive"))
      (node (ref "IC4") (pin "11") (pinfunction "FSYNC_11") (pintype "passive"))
      (node (ref "IC4") (pin "18") (pinfunction "GND_18") (pintype "passive"))
      (node (ref "J1") (pin "1") (pinfunction "TEMP1_1") (pintype "passive"))
      (node (ref "J1") (pin "3") (pinfunction "GND_3_3") (pintype "passive"))
      (node (ref "J1") (pin "9") (pinfunction "EP_9") (pintype "passive"))
      (node (ref "J2") (pin "5") (pinfunction "GND_5") (pintype "passive"))
      (node (ref "Q1") (pin "6") (pinfunction "S2_1_6") (pintype "passive"))
      (node (ref "Q1") (pin "7") (pinfunction "S2_2_7") (pintype "passive"))
      (node (ref "Q2") (pin "2") (pinfunction "S_2") (pintype "passive"))
      (node (ref "Q3") (pin "2") (pinfunction "S_2") (pintype "passive"))
      (node (ref "Q4") (pin "2") (pinfunction "S_2") (pintype "passive"))
      (node (ref "Q5") (pin "2") (pinfunction "S_2") (pintype "passive"))
      (node (ref "R1") (pin "2") (pinfunction "2_2") (pintype "passive"))
      (node (ref "R10") (pin "1") (pinfunction "1_1") (pintype "passive"))
      (node (ref "R14") (pin "1") (pinfunction "1_1") (pintype "passive"))
      (node (ref "R15") (pin "1") (pinfunction "1_1") (pintype "passive"))
      (node (ref "R18") (pin "1") (pinfunction "1_1") (pintype "passive"))
      (node (ref "R20") (pin "1") (pinfunction "1_1") (pintype "passive"))
      (node (ref "R22") (pin "1") (pinfunction "1_1") (pintype "passive"))
      (node (ref "R4") (pin "2") (pinfunction "2_2") (pintype "passive"))
      (node (ref "R5") (pin "1") (pinfunction "1_1") (pintype "passive"))
      (node (ref "R8") (pin "1") (pinfunction "1_1") (pintype "passive"))
      (node (ref "U1") (pin "20") (pinfunction "AREF_20") (pintype "passive"))
      (node (ref "U1") (pin "21") (pinfunction "GND_21") (pintype "power_in"))
      (node (ref "U1") (pin "3") (pinfunction "GND_3") (pintype "power_in"))
      (node (ref "U1") (pin "5") (pinfunction "GND_5") (pintype "power_in"))
      (node (ref "X1") (pin "2") (pinfunction "GND_2") (pintype "power_in"))
    )
    (net (code "45") (name "Net-(DS1-K)") (class "Default")
      (node (ref "DS1") (pin "2") (pinfunction "K_2") (pintype "passive"))
      (node (ref "R2") (pin "2") (pinfunction "2_2") (pintype "passive"))
    )
    (net (code "46") (name "Net-(DS2-K)") (class "Default")
      (node (ref "DS2") (pin "2") (pinfunction "K_2") (pintype "passive"))
      (node (ref "R3") (pin "2") (pinfunction "2_2") (pintype "passive"))
    )
    (net (code "47") (name "Net-(DS3-K)") (class "Default")
      (node (ref "DS3") (pin "2") (pinfunction "K_2") (pintype "passive"))
      (node (ref "R5") (pin "2") (pinfunction "2_2") (pintype "passive"))
    )
    (net (code "48") (name "Net-(DS4-K)") (class "Default")
      (node (ref "DS4") (pin "2") (pinfunction "K_2") (pintype "passive"))
      (node (ref "R14") (pin "2") (pinfunction "2_2") (pintype "passive"))
    )
    (net (code "49") (name "Net-(DS5-K)") (class "Default")
      (node (ref "DS5") (pin "2") (pinfunction "K_2") (pintype "passive"))
      (node (ref "R15") (pin "2") (pinfunction "2_2") (pintype "passive"))
    )
    (net (code "50") (name "Net-(IC4-CPOUT)") (class "Default")
      (node (ref "C11") (pin "1") (pinfunction "1_1") (pintype "passive"))
      (node (ref "IC4") (pin "20") (pinfunction "CPOUT_20") (pintype "passive"))
    )
    (net (code "51") (name "Net-(IC4-REGOUT)") (class "Default")
      (node (ref "C14") (pin "2") (pinfunction "2_2") (pintype "passive"))
      (node (ref "IC4") (pin "10") (pinfunction "REGOUT_10") (pintype "passive"))
    )
    (net (code "52") (name "Net-(Q2-G)") (class "Default")
      (node (ref "Q2") (pin "1") (pinfunction "G_1") (pintype "passive"))
      (node (ref "R17") (pin "1") (pinfunction "1_1") (pintype "passive"))
      (node (ref "R18") (pin "2") (pinfunction "2_2") (pintype "passive"))
    )
    (net (code "53") (name "Net-(Q3-G)") (class "Default")
      (node (ref "Q3") (pin "1") (pinfunction "G_1") (pintype "passive"))
      (node (ref "R19") (pin "1") (pinfunction "1_1") (pintype "passive"))
      (node (ref "R20") (pin "2") (pinfunction "2_2") (pintype "passive"))
    )
    (net (code "54") (name "Net-(Q4-G)") (class "Default")
      (node (ref "Q4") (pin "1") (pinfunction "G_1") (pintype "passive"))
      (node (ref "R21") (pin "1") (pinfunction "1_1") (pintype "passive"))
      (node (ref "R22") (pin "2") (pinfunction "2_2") (pintype "passive"))
    )
    (net (code "55") (name "Net-(Q5-G)") (class "Default")
      (node (ref "Q5") (pin "1") (pinfunction "G_1") (pintype "passive"))
      (node (ref "R23") (pin "1") (pinfunction "1_1") (pintype "passive"))
      (node (ref "R24") (pin "2") (pinfunction "2_2") (pintype "passive"))
    )
    (net (code "56") (name "Net-(U1-PB6(TOSC1{slash}XTAL1{slash}PCINT6))") (class "Default")
      (node (ref "U1") (pin "7") (pinfunction "PB6(TOSC1/XTAL1/PCINT6)_7") (pintype "bidirectional"))
      (node (ref "X1") (pin "1") (pinfunction "X1_1") (pintype "passive"))
    )
    (net (code "57") (name "Net-(U1-PB7(TOSC2{slash}XTAL2{slash}PCINT7))") (class "Default")
      (node (ref "U1") (pin "8") (pinfunction "PB7(TOSC2/XTAL2/PCINT7)_8") (pintype "bidirectional"))
      (node (ref "X1") (pin "3") (pinfunction "X2_3") (pintype "passive"))
    )
    (net (code "58") (name "unconnected-(IC1-TD-Pad4)") (class "Default")
      (node (ref "IC1") (pin "4") (pinfunction "TD_4") (pintype "passive+no_connect"))
    )
    (net (code "59") (name "unconnected-(IC2-NC-Pad6)") (class "Default")
      (node (ref "IC2") (pin "6") (pinfunction "NC_6") (pintype "passive+no_connect"))
    )
    (net (code "60") (name "unconnected-(IC3-CTS-Pad23)") (class "Default")
      (node (ref "IC3") (pin "23") (pinfunction "CTS_23") (pintype "passive+no_connect"))
    )
    (net (code "61") (name "unconnected-(IC3-DCD-Pad1)") (class "Default")
      (node (ref "IC3") (pin "1") (pinfunction "DCD_1") (pintype "passive+no_connect"))
    )
    (net (code "62") (name "unconnected-(IC3-DSR-Pad27)") (class "Default")
      (node (ref "IC3") (pin "27") (pinfunction "DSR_27") (pintype "passive+no_connect"))
    )
    (net (code "63") (name "unconnected-(IC3-NC_1-Pad10)") (class "Default")
      (node (ref "IC3") (pin "10") (pinfunction "NC_1_10") (pintype "passive+no_connect"))
    )
    (net (code "64") (name "unconnected-(IC3-NC_2-Pad13)") (class "Default")
      (node (ref "IC3") (pin "13") (pinfunction "NC_2_13") (pintype "passive+no_connect"))
    )
    (net (code "65") (name "unconnected-(IC3-NC_3-Pad14)") (class "Default")
      (node (ref "IC3") (pin "14") (pinfunction "NC_3_14") (pintype "passive+no_connect"))
    )
    (net (code "66") (name "unconnected-(IC3-NC_4-Pad15)") (class "Default")
      (node (ref "IC3") (pin "15") (pinfunction "NC_4_15") (pintype "passive+no_connect"))
    )
    (net (code "67") (name "unconnected-(IC3-NC_5-Pad16)") (class "Default")
      (node (ref "IC3") (pin "16") (pinfunction "NC_5_16") (pintype "passive+no_connect"))
    )
    (net (code "68") (name "unconnected-(IC3-NC_6-Pad17)") (class "Default")
      (node (ref "IC3") (pin "17") (pinfunction "NC_6_17") (pintype "passive+no_connect"))
    )
    (net (code "69") (name "unconnected-(IC3-NC_7-Pad18)") (class "Default")
      (node (ref "IC3") (pin "18") (pinfunction "NC_7_18") (pintype "passive+no_connect"))
    )
    (net (code "70") (name "unconnected-(IC3-NC_8-Pad19)") (class "Default")
      (node (ref "IC3") (pin "19") (pinfunction "NC_8_19") (pintype "passive+no_connect"))
    )
    (net (code "71") (name "unconnected-(IC3-NC_9-Pad20)") (class "Default")
      (node (ref "IC3") (pin "20") (pinfunction "NC_9_20") (pintype "passive+no_connect"))
    )
    (net (code "72") (name "unconnected-(IC3-NC_10-Pad21)") (class "Default")
      (node (ref "IC3") (pin "21") (pinfunction "NC_10_21") (pintype "passive+no_connect"))
    )
    (net (code "73") (name "unconnected-(IC3-NC_11-Pad22)") (class "Default")
      (node (ref "IC3") (pin "22") (pinfunction "NC_11_22") (pintype "passive+no_connect"))
    )
    (net (code "74") (name "unconnected-(IC3-RI-Pad2)") (class "Default")
      (node (ref "IC3") (pin "2") (pinfunction "RI_2") (pintype "passive+no_connect"))
    )
    (net (code "75") (name "unconnected-(IC3-RTS-Pad24)") (class "Default")
      (node (ref "IC3") (pin "24") (pinfunction "RTS_24") (pintype "passive+no_connect"))
    )
    (net (code "76") (name "unconnected-(IC3-SUSPEND-Pad12)") (class "Default")
      (node (ref "IC3") (pin "12") (pinfunction "SUSPEND_12") (pintype "passive+no_connect"))
    )
    (net (code "77") (name "unconnected-(IC3-~{RST}-Pad9)") (class "Default")
      (node (ref "IC3") (pin "9") (pinfunction "~{RST}_9") (pintype "passive+no_connect"))
    )
    (net (code "78") (name "unconnected-(IC3-~{SUSPEND}-Pad11)") (class "Default")
      (node (ref "IC3") (pin "11") (pinfunction "~{SUSPEND}_11") (pintype "passive+no_connect"))
    )
    (net (code "79") (name "unconnected-(IC4-AD0-Pad9)") (class "Default")
      (node (ref "IC4") (pin "9") (pinfunction "AD0_9") (pintype "passive+no_connect"))
    )
    (net (code "80") (name "unconnected-(IC4-AUX_CL-Pad7)") (class "Default")
      (node (ref "IC4") (pin "7") (pinfunction "AUX_CL_7") (pintype "passive+no_connect"))
    )
    (net (code "81") (name "unconnected-(IC4-AUX_DA-Pad6)") (class "Default")
      (node (ref "IC4") (pin "6") (pinfunction "AUX_DA_6") (pintype "passive+no_connect"))
    )
    (net (code "82") (name "unconnected-(IC4-EP-Pad25)") (class "Default")
      (node (ref "IC4") (pin "25") (pinfunction "EP_25") (pintype "passive+no_connect"))
    )
    (net (code "83") (name "unconnected-(IC4-INT-Pad12)") (class "Default")
      (node (ref "IC4") (pin "12") (pinfunction "INT_12") (pintype "passive+no_connect"))
    )
    (net (code "84") (name "unconnected-(IC4-NC_1-Pad2)") (class "Default")
      (node (ref "IC4") (pin "2") (pinfunction "NC_1_2") (pintype "passive+no_connect"))
    )
    (net (code "85") (name "unconnected-(IC4-NC_2-Pad3)") (class "Default")
      (node (ref "IC4") (pin "3") (pinfunction "NC_2_3") (pintype "passive+no_connect"))
    )
    (net (code "86") (name "unconnected-(IC4-NC_3-Pad4)") (class "Default")
      (node (ref "IC4") (pin "4") (pinfunction "NC_3_4") (pintype "passive+no_connect"))
    )
    (net (code "87") (name "unconnected-(IC4-NC_4-Pad5)") (class "Default")
      (node (ref "IC4") (pin "5") (pinfunction "NC_4_5") (pintype "passive+no_connect"))
    )
    (net (code "88") (name "unconnected-(IC4-NC_5-Pad14)") (class "Default")
      (node (ref "IC4") (pin "14") (pinfunction "NC_5_14") (pintype "passive+no_connect"))
    )
    (net (code "89") (name "unconnected-(IC4-NC_6-Pad15)") (class "Default")
      (node (ref "IC4") (pin "15") (pinfunction "NC_6_15") (pintype "passive+no_connect"))
    )
    (net (code "90") (name "unconnected-(IC4-NC_7-Pad16)") (class "Default")
      (node (ref "IC4") (pin "16") (pinfunction "NC_7_16") (pintype "passive+no_connect"))
    )
    (net (code "91") (name "unconnected-(IC4-NC_8-Pad17)") (class "Default")
      (node (ref "IC4") (pin "17") (pinfunction "NC_8_17") (pintype "passive+no_connect"))
    )
    (net (code "92") (name "unconnected-(IC4-RESV_1-Pad19)") (class "Default")
      (node (ref "IC4") (pin "19") (pinfunction "RESV_1_19") (pintype "passive+no_connect"))
    )
    (net (code "93") (name "unconnected-(IC4-RESV_2-Pad21)") (class "Default")
      (node (ref "IC4") (pin "21") (pinfunction "RESV_2_21") (pintype "passive+no_connect"))
    )
    (net (code "94") (name "unconnected-(IC4-RESV_3-Pad22)") (class "Default")
      (node (ref "IC4") (pin "22") (pinfunction "RESV_3_22") (pintype "passive+no_connect"))
    )
    (net (code "95") (name "unconnected-(J2-ID-Pad4)") (class "Default")
      (node (ref "J2") (pin "4") (pinfunction "ID_4") (pintype "passive+no_connect"))
    )
    (net (code "96") (name "unconnected-(J2-SHLD1-Pad6)") (class "Default")
      (node (ref "J2") (pin "6") (pinfunction "SHLD1_6") (pintype "passive+no_connect"))
    )
    (net (code "97") (name "unconnected-(J2-SHLD2-Pad7)") (class "Default")
      (node (ref "J2") (pin "7") (pinfunction "SHLD2_7") (pintype "passive+no_connect"))
    )
    (net (code "98") (name "unconnected-(J2-SHLD3-Pad8)") (class "Default")
      (node (ref "J2") (pin "8") (pinfunction "SHLD3_8") (pintype "passive+no_connect"))
    )
    (net (code "99") (name "unconnected-(J2-SHLD4-Pad9)") (class "Default")
      (node (ref "J2") (pin "9") (pinfunction "SHLD4_9") (pintype "passive+no_connect"))
    )
    (net (code "100") (name "unconnected-(J2-SHLD5-Pad10)") (class "Default")
      (node (ref "J2") (pin "10") (pinfunction "SHLD5_10") (pintype "passive+no_connect"))
    )
    (net (code "101") (name "unconnected-(J2-SHLD6-Pad11)") (class "Default")
      (node (ref "J2") (pin "11") (pinfunction "SHLD6_11") (pintype "passive+no_connect"))
    )
    (net (code "102") (name "unconnected-(Q1-D12_1-Pad1)") (class "Default")
      (node (ref "Q1") (pin "1") (pinfunction "D12_1_1") (pintype "passive+no_connect"))
    )
    (net (code "103") (name "unconnected-(Q1-D12_2-Pad8)") (class "Default")
      (node (ref "Q1") (pin "8") (pinfunction "D12_2_8") (pintype "passive+no_connect"))
    )
    (net (code "104") (name "unconnected-(R24-Pad1)") (class "Default")
      (node (ref "R24") (pin "1") (pinfunction "1_1") (pintype "passive"))
    )
    (net (code "105") (name "unconnected-(SW1-MNT_1-Pad4)") (class "Default")
      (node (ref "SW1") (pin "4") (pinfunction "MNT_1_4") (pintype "passive+no_connect"))
    )
    (net (code "106") (name "unconnected-(SW1-MNT_2-Pad5)") (class "Default")
      (node (ref "SW1") (pin "5") (pinfunction "MNT_2_5") (pintype "passive+no_connect"))
    )
    (net (code "107") (name "unconnected-(SW1-Pad3)") (class "Default")
      (node (ref "SW1") (pin "3") (pinfunction "3_3") (pintype "passive+no_connect"))
    )
    (net (code "108") (name "unconnected-(U1-ADC6-Pad19)") (class "Default")
      (node (ref "U1") (pin "19") (pinfunction "ADC6_19") (pintype "passive"))
    )
    (net (code "109") (name "unconnected-(U1-ADC7-Pad22)") (class "Default")
      (node (ref "U1") (pin "22") (pinfunction "ADC7_22") (pintype "passive"))
    )
    (net (code "110") (name "unconnected-(U1-PC1(ADC1{slash}PCINT9)-Pad24)") (class "Default")
      (node (ref "U1") (pin "24") (pinfunction "PC1(ADC1/PCINT9)_24") (pintype "bidirectional"))
    )
    (net (code "111") (name "unconnected-(U1-PC2(ADC2{slash}PCINT10)-Pad25)") (class "Default")
      (node (ref "U1") (pin "25") (pinfunction "PC2(ADC2/PCINT10)_25") (pintype "bidirectional"))
    )
    (net (code "112") (name "unconnected-(U1-PC3(ADC3{slash}PCINT11)-Pad26)") (class "Default")
      (node (ref "U1") (pin "26") (pinfunction "PC3(ADC3/PCINT11)_26") (pintype "bidirectional"))
    )
  )
)
